# LED_board_2.net
KiCad netlist of a schematic drawn in EAGLE
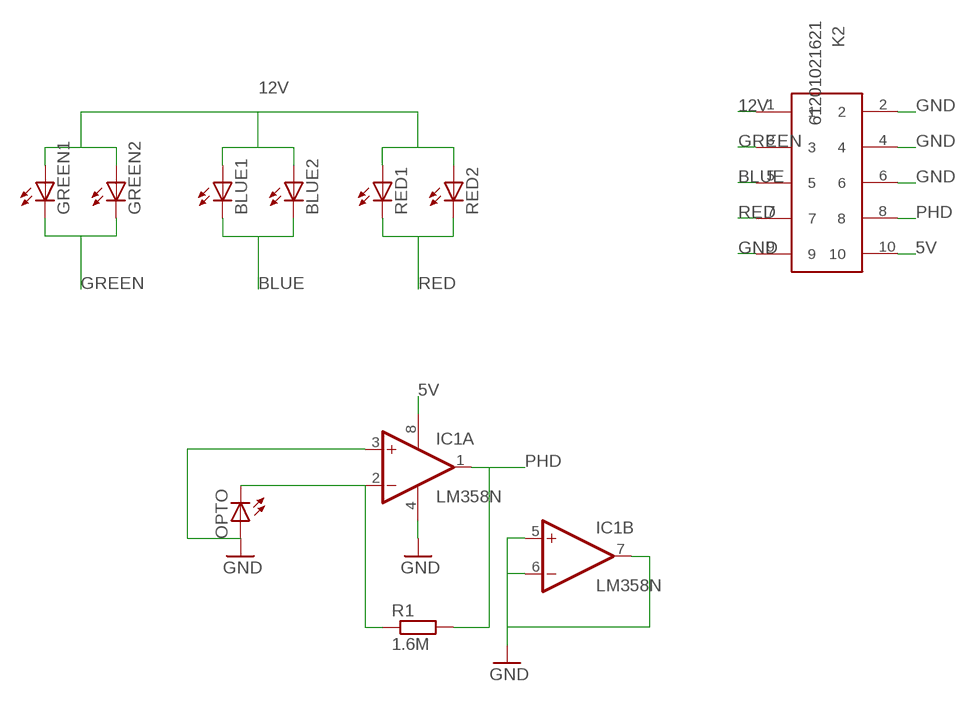
[diagram p0: schematic, sheet 1]

(export (version "E")
  (design (tool "Eeschema 10.0.6"))
  (components
    (comp (ref "BLUE1")
      (value "LED5MM")
      (footprint "eagle-import:LED5MM")
      (libsource (lib "eagle-import") (part "LED5MM"))
    )
    (comp (ref "BLUE2")
      (value "LED5MM")
      (footprint "eagle-import:LED5MM")
      (libsource (lib "eagle-import") (part "LED5MM"))
    )
    (comp (ref "GREEN1")
      (value "LED5MM")
      (footprint "eagle-import:LED5MM")
      (libsource (lib "eagle-import") (part "LED5MM"))
    )
    (comp (ref "GREEN2")
      (value "LED5MM")
      (footprint "eagle-import:LED5MM")
      (libsource (lib "eagle-import") (part "LED5MM"))
    )
    (comp (ref "IC1")
      (value "LM358N")
      (footprint "eagle-import:DIL08")
      (libsource (lib "eagle-import") (part "LM358N"))
    )
    (comp (ref "K2")
      (value "61201021621")
      (footprint "eagle-import:61201021621")
      (libsource (lib "eagle-import") (part "61201021621"))
    )
    (comp (ref "OPTO")
      (value "LED5MM")
      (footprint "eagle-import:LED5MM")
      (libsource (lib "eagle-import") (part "LED5MM"))
    )
    (comp (ref "R1")
      (value "1.6M")
      (footprint "eagle-import:0207_10")
      (libsource (lib "eagle-import") (part "R-EU_0207/10"))
    )
    (comp (ref "RED1")
      (value "LED5MM")
      (footprint "eagle-import:LED5MM")
      (libsource (lib "eagle-import") (part "LED5MM"))
    )
    (comp (ref "RED2")
      (value "LED5MM")
      (footprint "eagle-import:LED5MM")
      (libsource (lib "eagle-import") (part "LED5MM"))
    )
  )
  (nets
    (net (code "1") (name "/5V") (class "Default")
      (node (ref "IC1") (pin "8") (pinfunction "V+_8") (pintype "power_in"))
      (node (ref "K2") (pin "10") (pinfunction "10_10") (pintype "passive"))
    )
    (net (code "2") (name "/12V") (class "Default")
      (node (ref "BLUE1") (pin "A") (pinfunction "A_A") (pintype "passive"))
      (node (ref "BLUE2") (pin "A") (pinfunction "A_A") (pintype "passive"))
      (node (ref "GREEN1") (pin "A") (pinfunction "A_A") (pintype "passive"))
      (node (ref "GREEN2") (pin "A") (pinfunction "A_A") (pintype "passive"))
      (node (ref "K2") (pin "1") (pinfunction "1_1") (pintype "passive"))
      (node (ref "RED1") (pin "A") (pinfunction "A_A") (pintype "passive"))
      (node (ref "RED2") (pin "A") (pinfunction "A_A") (pintype "passive"))
    )
    (net (code "3") (name "/BLUE") (class "Default")
      (node (ref "BLUE1") (pin "K") (pinfunction "C_K") (pintype "passive"))
      (node (ref "BLUE2") (pin "K") (pinfunction "C_K") (pintype "passive"))
      (node (ref "K2") (pin "5") (pinfunction "5_5") (pintype "passive"))
    )
    (net (code "4") (name "/GREEN") (class "Default")
      (node (ref "GREEN1") (pin "K") (pinfunction "C_K") (pintype "passive"))
      (node (ref "GREEN2") (pin "K") (pinfunction "C_K") (pintype "passive"))
      (node (ref "K2") (pin "3") (pinfunction "3_3") (pintype "passive"))
    )
    (net (code "5") (name "/PHD") (class "Default")
      (node (ref "IC1") (pin "1") (pinfunction "OUT_1") (pintype "output"))
      (node (ref "K2") (pin "8") (pinfunction "8_8") (pintype "passive"))
      (node (ref "R1") (pin "2") (pinfunction "2_2") (pintype "passive"))
    )
    (net (code "6") (name "/RED") (class "Default")
      (node (ref "K2") (pin "7") (pinfunction "7_7") (pintype "passive"))
      (node (ref "RED1") (pin "K") (pinfunction "C_K") (pintype "passive"))
      (node (ref "RED2") (pin "K") (pinfunction "C_K") (pintype "passive"))
    )
    (net (code "7") (name "GND") (class "Default")
      (node (ref "IC1") (pin "3") (pinfunction "+IN_3") (pintype "input"))
      (node (ref "IC1") (pin "4") (pinfunction "V-_4") (pintype "power_in"))
      (node (ref "IC1") (pin "5") (pinfunction "+IN_5") (pintype "input"))
      (node (ref "IC1") (pin "6") (pinfunction "-IN_6") (pintype "input"))
      (node (ref "IC1") (pin "7") (pinfunction "OUT_7") (pintype "output"))
      (node (ref "K2") (pin "2") (pinfunction "2_2") (pintype "passive"))
      (node (ref "K2") (pin "4") (pinfunction "4_4") (pintype "passive"))
      (node (ref "K2") (pin "6") (pinfunction "6_6") (pintype "passive"))
      (node (ref "K2") (pin "9") (pinfunction "9_9") (pintype "passive"))
      (node (ref "OPTO") (pin "A") (pinfunction "A_A") (pintype "passive"))
    )
    (net (code "8") (name "Net-(IC1A--IN)") (class "Default")
      (node (ref "IC1") (pin "2") (pinfunction "-IN_2") (pintype "input"))
      (node (ref "OPTO") (pin "K") (pinfunction "C_K") (pintype "passive"))
      (node (ref "R1") (pin "1") (pinfunction "1_1") (pintype "passive"))
    )
  )
)
